# 01_XOR.net
KiCad netlist of a schematic drawn in EAGLE
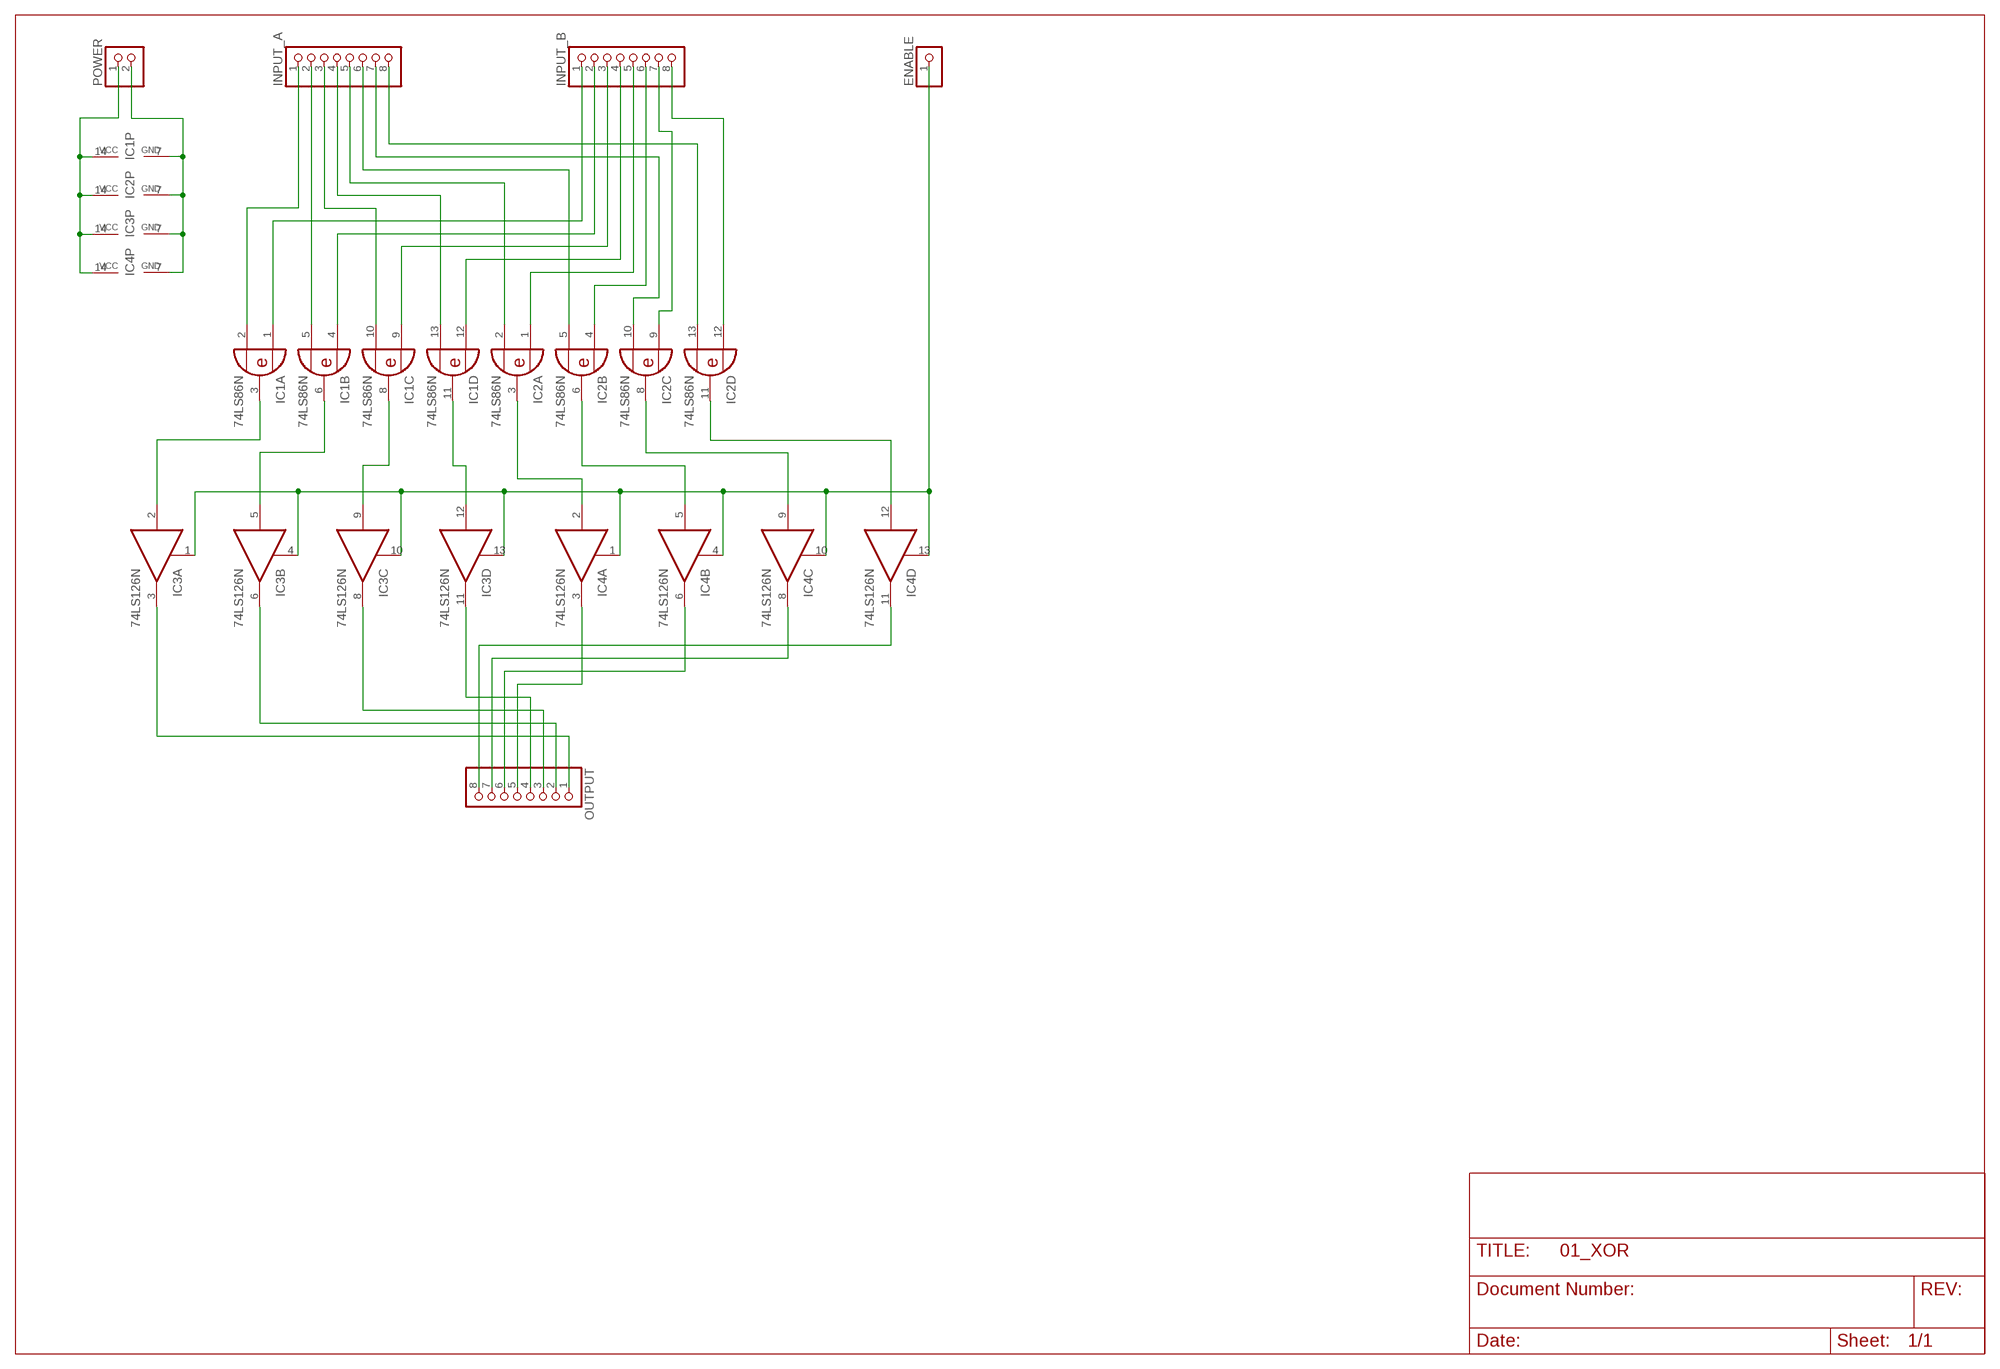
[diagram p0: schematic, sheet 1]

(export (version "E")
  (design (tool "Eeschema 10.0.6"))
  (components
    (comp (ref "ENABLE")
      (value "PINHD-1X1")
      (footprint "eagle-import:1X01")
      (libsource (lib "eagle-import") (part "PINHD-1X1"))
    )
    (comp (ref "IC1")
      (value "74LS86N")
      (footprint "eagle-import:DIL14")
      (libsource (lib "eagle-import") (part "7486NLS"))
    )
    (comp (ref "IC2")
      (value "74LS86N")
      (footprint "eagle-import:DIL14")
      (libsource (lib "eagle-import") (part "7486NLS"))
    )
    (comp (ref "IC3")
      (value "74LS126N")
      (footprint "eagle-import:DIL14")
      (libsource (lib "eagle-import") (part "74126NLS"))
    )
    (comp (ref "IC4")
      (value "74LS126N")
      (footprint "eagle-import:DIL14")
      (libsource (lib "eagle-import") (part "74126NLS"))
    )
    (comp (ref "INPUT_A")
      (value "PINHD-1X8")
      (footprint "eagle-import:1X08")
      (libsource (lib "eagle-import") (part "PINHD-1X8"))
    )
    (comp (ref "INPUT_B")
      (value "PINHD-1X8")
      (footprint "eagle-import:1X08")
      (libsource (lib "eagle-import") (part "PINHD-1X8"))
    )
    (comp (ref "OUTPUT")
      (value "PINHD-1X8")
      (footprint "eagle-import:1X08")
      (libsource (lib "eagle-import") (part "PINHD-1X8"))
    )
    (comp (ref "POWER")
      (value "PINHD-1X2")
      (footprint "eagle-import:1X02")
      (libsource (lib "eagle-import") (part "PINHD-1X2"))
    )
  )
  (nets
    (net (code "1") (name "Net-(IC1A-I0)") (class "Default")
      (node (ref "IC1") (pin "1") (pinfunction "I0_1") (pintype "input"))
      (node (ref "INPUT_B") (pin "1") (pinfunction "1_1") (pintype "passive"))
    )
    (net (code "2") (name "Net-(IC1A-I1)") (class "Default")
      (node (ref "IC1") (pin "2") (pinfunction "I1_2") (pintype "input"))
      (node (ref "INPUT_A") (pin "1") (pinfunction "1_1") (pintype "passive"))
    )
    (net (code "3") (name "Net-(IC1A-O)") (class "Default")
      (node (ref "IC1") (pin "3") (pinfunction "O_3") (pintype "output"))
      (node (ref "IC3") (pin "2") (pinfunction "I_2") (pintype "input"))
    )
    (net (code "4") (name "Net-(IC1B-I0)") (class "Default")
      (node (ref "IC1") (pin "4") (pinfunction "I0_4") (pintype "input"))
      (node (ref "INPUT_B") (pin "2") (pinfunction "2_2") (pintype "passive"))
    )
    (net (code "5") (name "Net-(IC1B-I1)") (class "Default")
      (node (ref "IC1") (pin "5") (pinfunction "I1_5") (pintype "input"))
      (node (ref "INPUT_A") (pin "2") (pinfunction "2_2") (pintype "passive"))
    )
    (net (code "6") (name "Net-(IC1B-O)") (class "Default")
      (node (ref "IC1") (pin "6") (pinfunction "O_6") (pintype "output"))
      (node (ref "IC3") (pin "5") (pinfunction "I_5") (pintype "input"))
    )
    (net (code "7") (name "Net-(IC1C-I0)") (class "Default")
      (node (ref "IC1") (pin "9") (pinfunction "I0_9") (pintype "input"))
      (node (ref "INPUT_B") (pin "3") (pinfunction "3_3") (pintype "passive"))
    )
    (net (code "8") (name "Net-(IC1C-I1)") (class "Default")
      (node (ref "IC1") (pin "10") (pinfunction "I1_10") (pintype "input"))
      (node (ref "INPUT_A") (pin "3") (pinfunction "3_3") (pintype "passive"))
    )
    (net (code "9") (name "Net-(IC1C-O)") (class "Default")
      (node (ref "IC1") (pin "8") (pinfunction "O_8") (pintype "output"))
      (node (ref "IC3") (pin "9") (pinfunction "I_9") (pintype "input"))
    )
    (net (code "10") (name "Net-(IC1D-I0)") (class "Default")
      (node (ref "IC1") (pin "12") (pinfunction "I0_12") (pintype "input"))
      (node (ref "INPUT_B") (pin "4") (pinfunction "4_4") (pintype "passive"))
    )
    (net (code "11") (name "Net-(IC1D-I1)") (class "Default")
      (node (ref "IC1") (pin "13") (pinfunction "I1_13") (pintype "input"))
      (node (ref "INPUT_A") (pin "4") (pinfunction "4_4") (pintype "passive"))
    )
    (net (code "12") (name "Net-(IC1D-O)") (class "Default")
      (node (ref "IC1") (pin "11") (pinfunction "O_11") (pintype "output"))
      (node (ref "IC3") (pin "12") (pinfunction "I_12") (pintype "input"))
    )
    (net (code "13") (name "Net-(IC1E-GND)") (class "Default")
      (node (ref "IC1") (pin "7") (pinfunction "GND_7") (pintype "power_in"))
      (node (ref "IC2") (pin "7") (pinfunction "GND_7") (pintype "power_in"))
      (node (ref "IC3") (pin "7") (pinfunction "GND_7") (pintype "power_in"))
      (node (ref "IC4") (pin "7") (pinfunction "GND_7") (pintype "power_in"))
      (node (ref "POWER") (pin "2") (pinfunction "2_2") (pintype "passive"))
    )
    (net (code "14") (name "Net-(IC1E-VCC)") (class "Default")
      (node (ref "IC1") (pin "14") (pinfunction "VCC_14") (pintype "power_in"))
      (node (ref "IC2") (pin "14") (pinfunction "VCC_14") (pintype "power_in"))
      (node (ref "IC3") (pin "14") (pinfunction "VCC_14") (pintype "power_in"))
      (node (ref "IC4") (pin "14") (pinfunction "VCC_14") (pintype "power_in"))
      (node (ref "POWER") (pin "1") (pinfunction "1_1") (pintype "passive"))
    )
    (net (code "15") (name "Net-(IC2A-I0)") (class "Default")
      (node (ref "IC2") (pin "1") (pinfunction "I0_1") (pintype "input"))
      (node (ref "INPUT_B") (pin "5") (pinfunction "5_5") (pintype "passive"))
    )
    (net (code "16") (name "Net-(IC2A-I1)") (class "Default")
      (node (ref "IC2") (pin "2") (pinfunction "I1_2") (pintype "input"))
      (node (ref "INPUT_A") (pin "5") (pinfunction "5_5") (pintype "passive"))
    )
    (net (code "17") (name "Net-(IC2A-O)") (class "Default")
      (node (ref "IC2") (pin "3") (pinfunction "O_3") (pintype "output"))
      (node (ref "IC4") (pin "2") (pinfunction "I_2") (pintype "input"))
    )
    (net (code "18") (name "Net-(IC2B-I0)") (class "Default")
      (node (ref "IC2") (pin "4") (pinfunction "I0_4") (pintype "input"))
      (node (ref "INPUT_B") (pin "6") (pinfunction "6_6") (pintype "passive"))
    )
    (net (code "19") (name "Net-(IC2B-I1)") (class "Default")
      (node (ref "IC2") (pin "5") (pinfunction "I1_5") (pintype "input"))
      (node (ref "INPUT_A") (pin "6") (pinfunction "6_6") (pintype "passive"))
    )
    (net (code "20") (name "Net-(IC2B-O)") (class "Default")
      (node (ref "IC2") (pin "6") (pinfunction "O_6") (pintype "output"))
      (node (ref "IC4") (pin "5") (pinfunction "I_5") (pintype "input"))
    )
    (net (code "21") (name "Net-(IC2C-I0)") (class "Default")
      (node (ref "IC2") (pin "9") (pinfunction "I0_9") (pintype "input"))
      (node (ref "INPUT_B") (pin "7") (pinfunction "7_7") (pintype "passive"))
    )
    (net (code "22") (name "Net-(IC2C-I1)") (class "Default")
      (node (ref "IC2") (pin "10") (pinfunction "I1_10") (pintype "input"))
      (node (ref "INPUT_A") (pin "7") (pinfunction "7_7") (pintype "passive"))
    )
    (net (code "23") (name "Net-(IC2C-O)") (class "Default")
      (node (ref "IC2") (pin "8") (pinfunction "O_8") (pintype "output"))
      (node (ref "IC4") (pin "9") (pinfunction "I_9") (pintype "input"))
    )
    (net (code "24") (name "Net-(IC2D-I0)") (class "Default")
      (node (ref "IC2") (pin "12") (pinfunction "I0_12") (pintype "input"))
      (node (ref "INPUT_B") (pin "8") (pinfunction "8_8") (pintype "passive"))
    )
    (net (code "25") (name "Net-(IC2D-I1)") (class "Default")
      (node (ref "IC2") (pin "13") (pinfunction "I1_13") (pintype "input"))
      (node (ref "INPUT_A") (pin "8") (pinfunction "8_8") (pintype "passive"))
    )
    (net (code "26") (name "Net-(IC2D-O)") (class "Default")
      (node (ref "IC2") (pin "11") (pinfunction "O_11") (pintype "output"))
      (node (ref "IC4") (pin "12") (pinfunction "I_12") (pintype "input"))
    )
    (net (code "27") (name "Net-(IC3A-O)") (class "Default")
      (node (ref "IC3") (pin "3") (pinfunction "O_3") (pintype "output"))
      (node (ref "OUTPUT") (pin "1") (pinfunction "1_1") (pintype "passive"))
    )
    (net (code "28") (name "Net-(IC3A-OE)") (class "Default")
      (node (ref "ENABLE") (pin "1") (pinfunction "1_1") (pintype "passive"))
      (node (ref "IC3") (pin "1") (pinfunction "OE_1") (pintype "input"))
      (node (ref "IC3") (pin "10") (pinfunction "OE_10") (pintype "input"))
      (node (ref "IC3") (pin "13") (pinfunction "OE_13") (pintype "input"))
      (node (ref "IC3") (pin "4") (pinfunction "OE_4") (pintype "input"))
      (node (ref "IC4") (pin "1") (pinfunction "OE_1") (pintype "input"))
      (node (ref "IC4") (pin "10") (pinfunction "OE_10") (pintype "input"))
      (node (ref "IC4") (pin "13") (pinfunction "OE_13") (pintype "input"))
      (node (ref "IC4") (pin "4") (pinfunction "OE_4") (pintype "input"))
    )
    (net (code "29") (name "Net-(IC3B-O)") (class "Default")
      (node (ref "IC3") (pin "6") (pinfunction "O_6") (pintype "output"))
      (node (ref "OUTPUT") (pin "2") (pinfunction "2_2") (pintype "passive"))
    )
    (net (code "30") (name "Net-(IC3C-O)") (class "Default")
      (node (ref "IC3") (pin "8") (pinfunction "O_8") (pintype "output"))
      (node (ref "OUTPUT") (pin "3") (pinfunction "3_3") (pintype "passive"))
    )
    (net (code "31") (name "Net-(IC3D-O)") (class "Default")
      (node (ref "IC3") (pin "11") (pinfunction "O_11") (pintype "output"))
      (node (ref "OUTPUT") (pin "4") (pinfunction "4_4") (pintype "passive"))
    )
    (net (code "32") (name "Net-(IC4A-O)") (class "Default")
      (node (ref "IC4") (pin "3") (pinfunction "O_3") (pintype "output"))
      (node (ref "OUTPUT") (pin "5") (pinfunction "5_5") (pintype "passive"))
    )
    (net (code "33") (name "Net-(IC4B-O)") (class "Default")
      (node (ref "IC4") (pin "6") (pinfunction "O_6") (pintype "output"))
      (node (ref "OUTPUT") (pin "6") (pinfunction "6_6") (pintype "passive"))
    )
    (net (code "34") (name "Net-(IC4C-O)") (class "Default")
      (node (ref "IC4") (pin "8") (pinfunction "O_8") (pintype "output"))
      (node (ref "OUTPUT") (pin "7") (pinfunction "7_7") (pintype "passive"))
    )
    (net (code "35") (name "Net-(IC4D-O)") (class "Default")
      (node (ref "IC4") (pin "11") (pinfunction "O_11") (pintype "output"))
      (node (ref "OUTPUT") (pin "8") (pinfunction "8_8") (pintype "passive"))
    )
  )
)
